# RevisionB.net
KiCad netlist of a schematic drawn in EAGLE
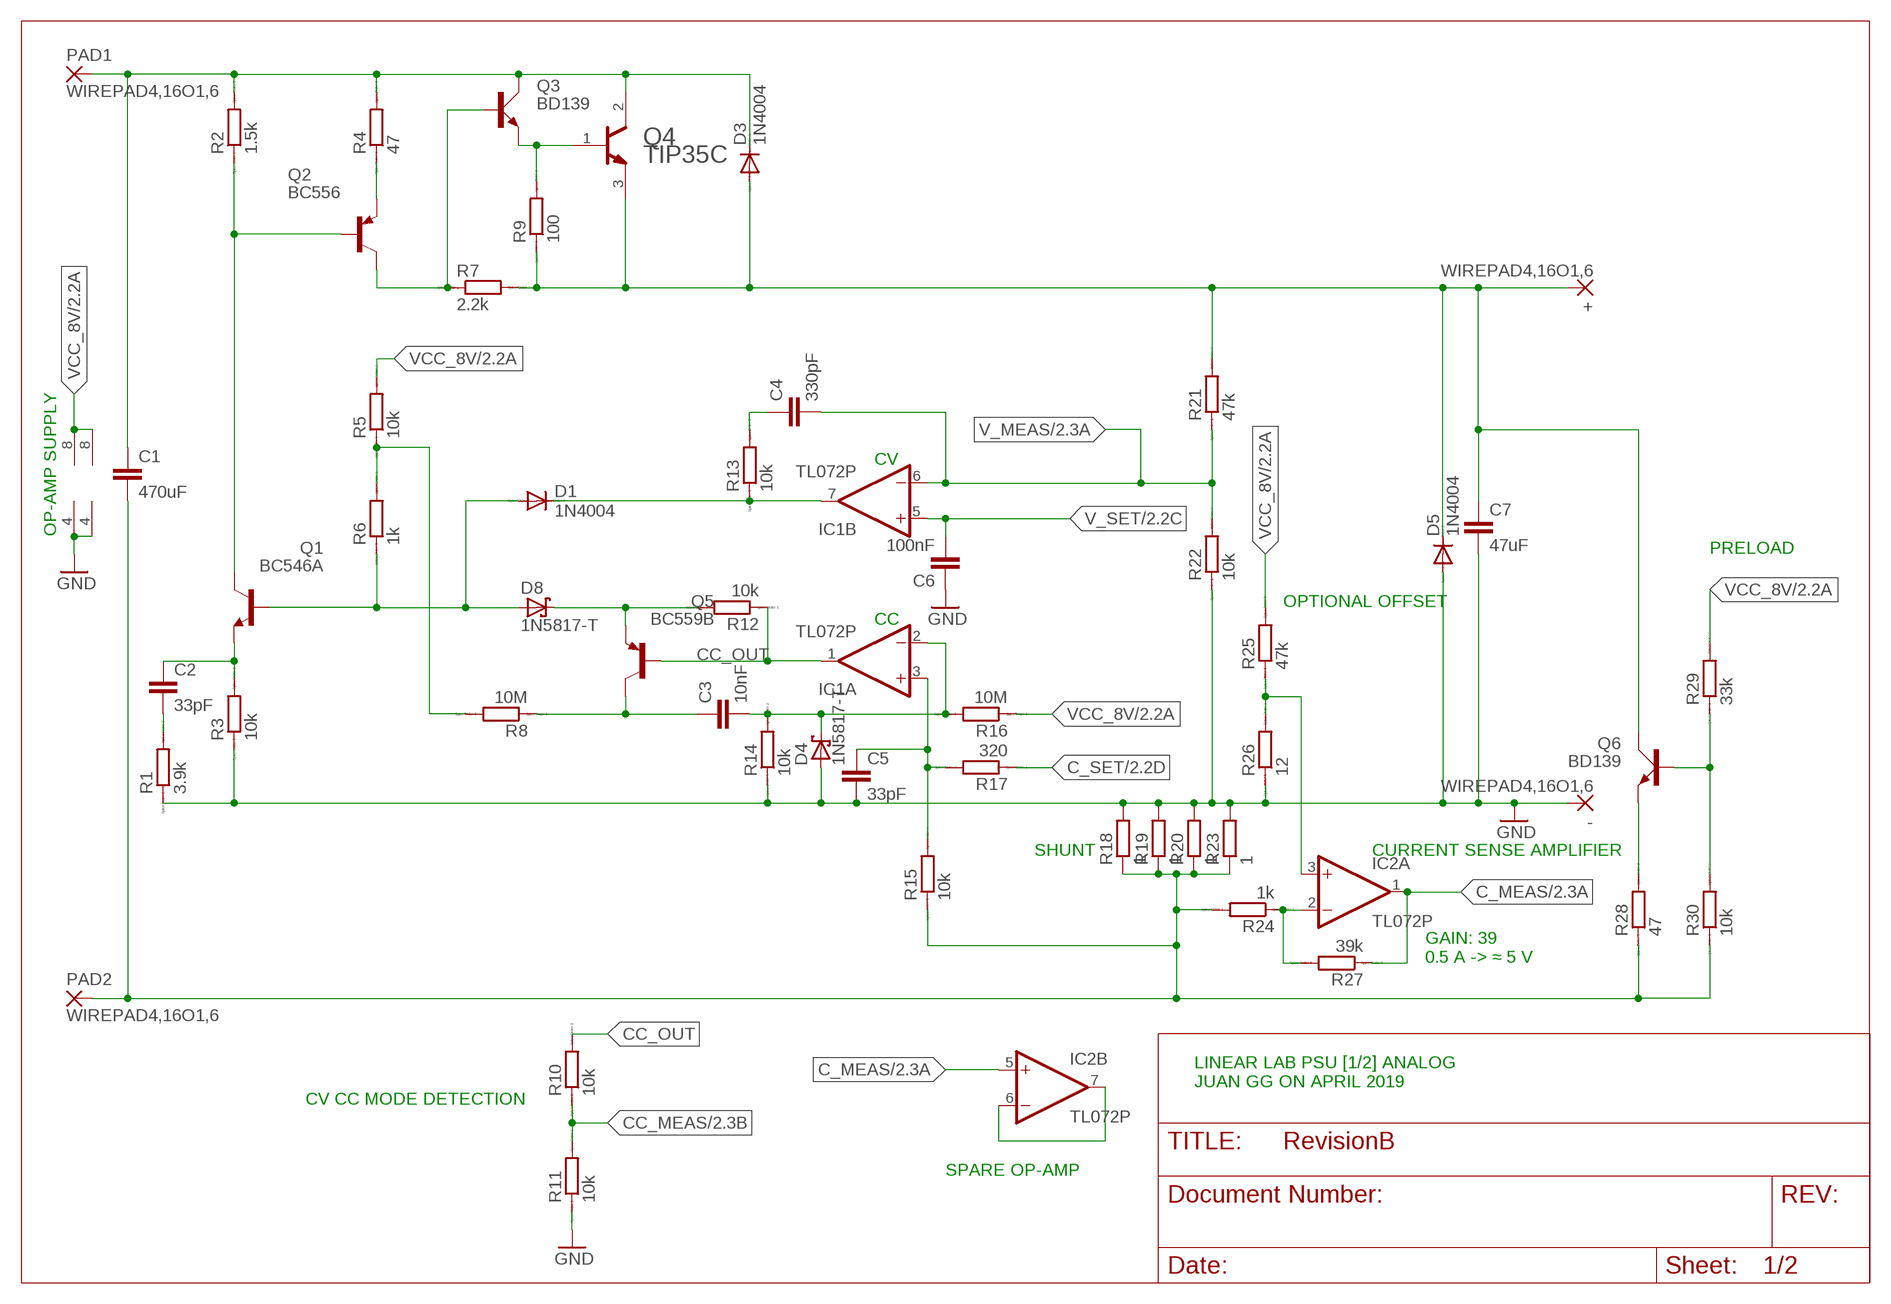
[diagram p0: schematic, sheet 1]
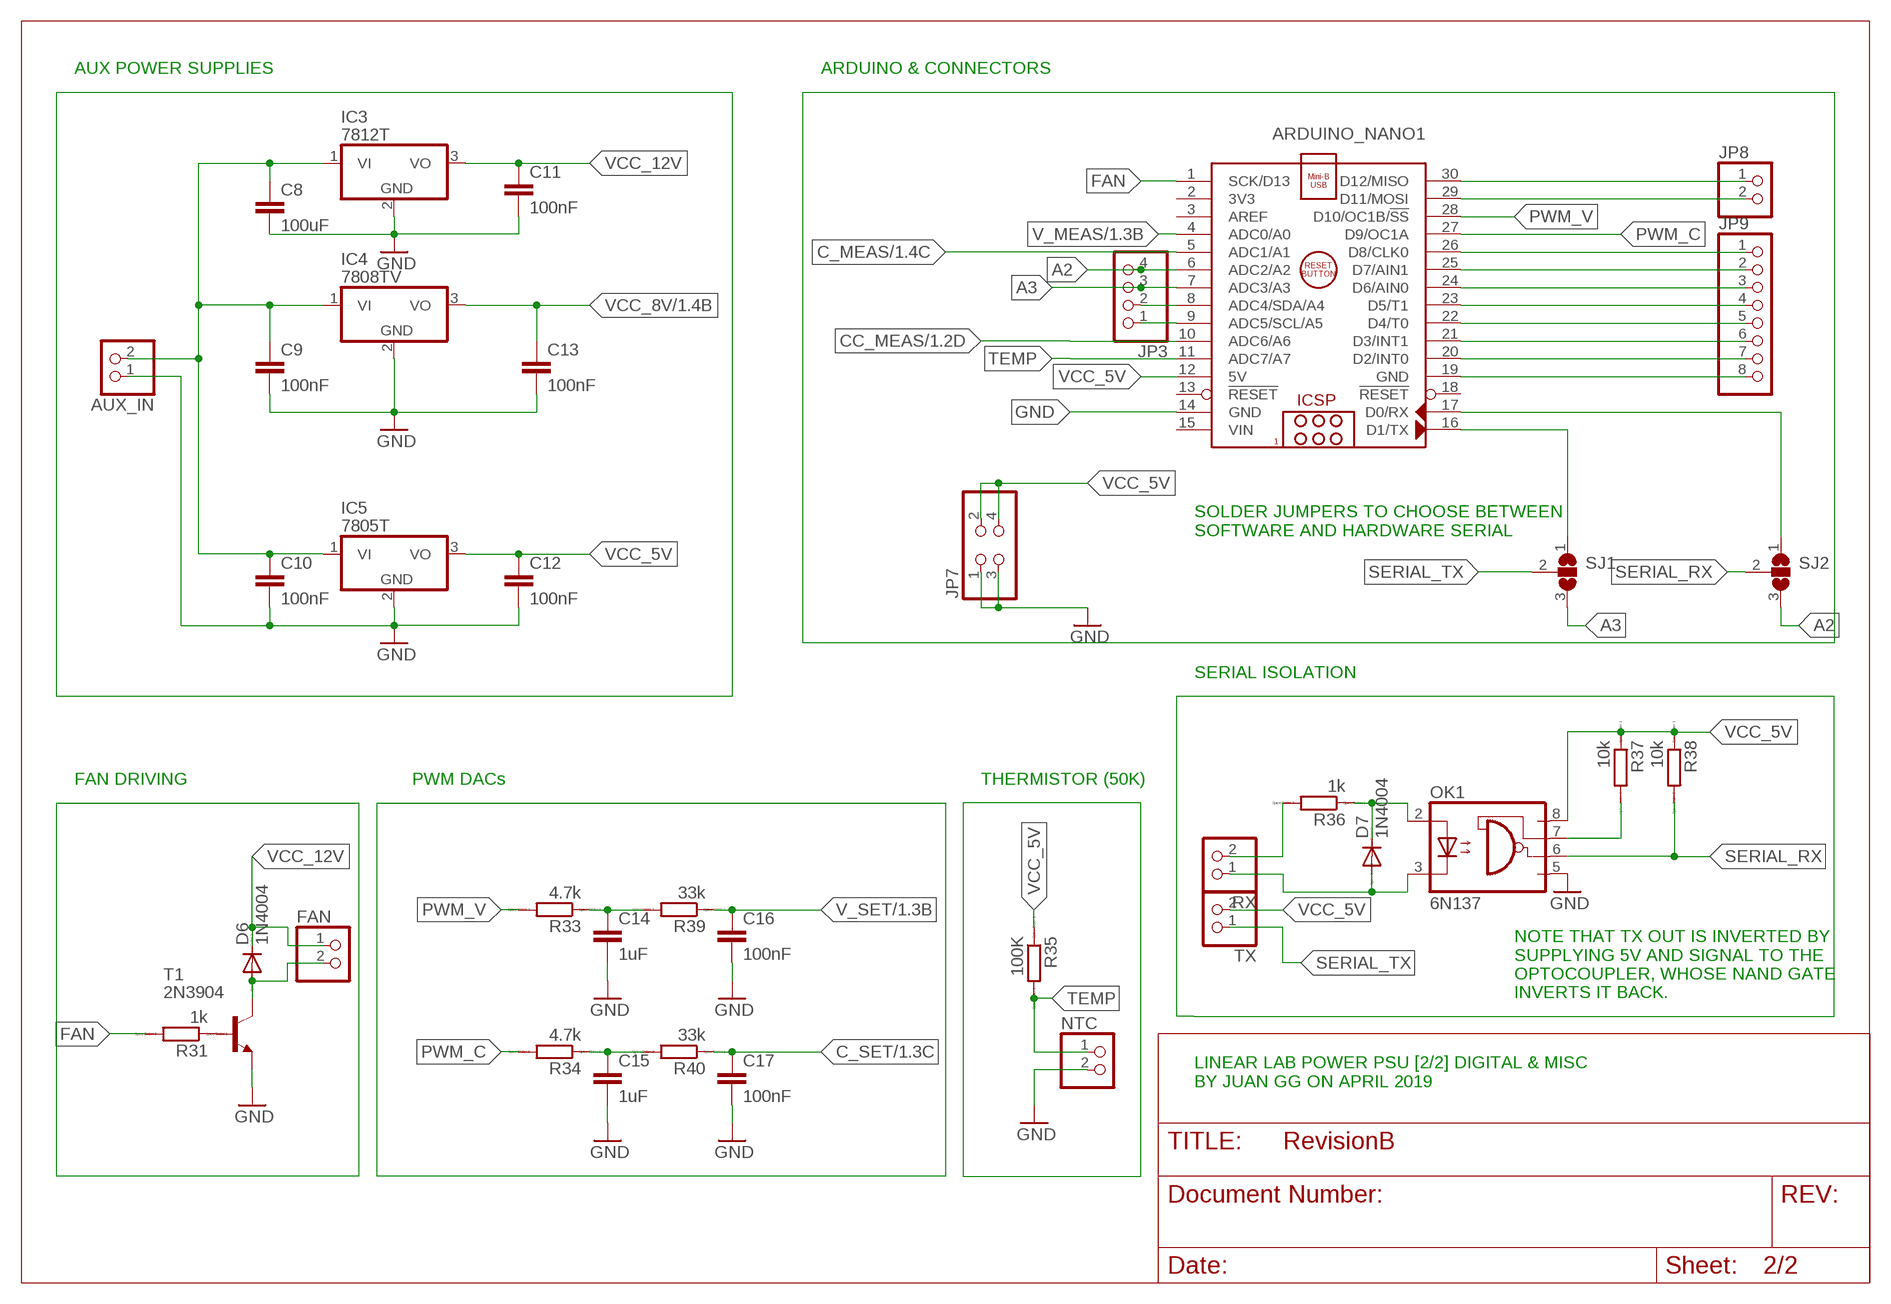
[diagram p1: schematic, sheet 2]

(export (version "E")
  (design (tool "Eeschema 10.0.6"))
  (components
    (comp (ref "+")
      (value "WIREPAD4,16O1,6")
      (footprint "eagle-import:4,16O1,6")
      (libsource (lib "eagle-import") (part "WIREPAD4,16O1,6"))
    )
    (comp (ref "-")
      (value "WIREPAD4,16O1,6")
      (footprint "eagle-import:4,16O1,6")
      (libsource (lib "eagle-import") (part "WIREPAD4,16O1,6"))
    )
    (comp (ref "C1")
      (value "470uF")
      (footprint "eagle-import:C5B7.2")
      (libsource (lib "eagle-import") (part "C5/7.2"))
    )
    (comp (ref "C2")
      (value "33pF")
      (footprint "eagle-import:C2.5-2")
      (libsource (lib "eagle-import") (part "C2.5/2"))
    )
    (comp (ref "C3")
      (value "10nF")
      (footprint "eagle-import:C2.5-2")
      (libsource (lib "eagle-import") (part "C2.5/2"))
    )
    (comp (ref "C4")
      (value "330pF")
      (footprint "eagle-import:C2.5-2")
      (libsource (lib "eagle-import") (part "C2.5/2"))
    )
    (comp (ref "C5")
      (value "33pF")
      (footprint "eagle-import:C2.5-2")
      (libsource (lib "eagle-import") (part "C2.5/2"))
    )
    (comp (ref "C6")
      (value "100nF")
      (footprint "eagle-import:C2.5-2")
      (libsource (lib "eagle-import") (part "C2.5/2"))
    )
    (comp (ref "C7")
      (value "47uF")
      (footprint "eagle-import:C5B7.2")
      (libsource (lib "eagle-import") (part "C5/7.2"))
    )
    (comp (ref "D1")
      (value "1N4004")
      (footprint "eagle-import:DO41-10")
      (libsource (lib "eagle-import") (part "1N4004"))
    )
    (comp (ref "D3")
      (value "1N4004")
      (footprint "eagle-import:DO41-10")
      (libsource (lib "eagle-import") (part "1N4004"))
    )
    (comp (ref "D4")
      (value "1N5817-T")
      (footprint "eagle-import:DO41-7.6")
      (libsource (lib "eagle-import") (part "1N5817-T"))
    )
    (comp (ref "D5")
      (value "1N4004")
      (footprint "eagle-import:DO41-10")
      (libsource (lib "eagle-import") (part "1N4004"))
    )
    (comp (ref "D8")
      (value "1N5817-T")
      (footprint "eagle-import:DO41-7.6")
      (libsource (lib "eagle-import") (part "1N5817-T"))
    )
    (comp (ref "IC1")
      (value "TL072P")
      (footprint "eagle-import:DIL08")
      (libsource (lib "eagle-import") (part "TL072P"))
    )
    (comp (ref "IC2")
      (value "TL072P")
      (footprint "eagle-import:DIL08")
      (libsource (lib "eagle-import") (part "TL072P"))
    )
    (comp (ref "PAD1")
      (value "WIREPAD4,16O1,6")
      (footprint "eagle-import:4,16O1,6")
      (libsource (lib "eagle-import") (part "WIREPAD4,16O1,6"))
    )
    (comp (ref "PAD2")
      (value "WIREPAD4,16O1,6")
      (footprint "eagle-import:4,16O1,6")
      (libsource (lib "eagle-import") (part "WIREPAD4,16O1,6"))
    )
    (comp (ref "Q1")
      (value "BC546A")
      (footprint "eagle-import:TO92-EBC")
      (libsource (lib "eagle-import") (part "BC546A"))
    )
    (comp (ref "Q2")
      (value "BC556")
      (footprint "eagle-import:TO92-EBC")
      (libsource (lib "eagle-import") (part "BC556"))
    )
    (comp (ref "Q3")
      (value "BD139")
      (footprint "eagle-import:TO126AV")
      (libsource (lib "eagle-import") (part "BD139"))
    )
    (comp (ref "Q4")
      (value "STMICROELECTRONICS_TIP35CSTMICROELECTRONICS_TIP35C_0_0")
      (footprint "eagle-import:STMICROELECTRONICS_TIP35C_0")
      (fields
        (field (name "DIGIKEY_PART_NUMBER") "497-2609-5-ND")
        (field (name "MF") "STMicroelectronics")
        (field (name "MOUSER_PART_NUMBER") "511-TIP35C")
      )
      (libsource (lib "eagle-import") (part "STMICROELECTRONICS_TIP35CSTMICROELECTRONICS_TIP35C_0_0"))
    )
    (comp (ref "Q5")
      (value "BC559B")
      (footprint "eagle-import:TO92-EBC")
      (libsource (lib "eagle-import") (part "BC559B"))
    )
    (comp (ref "Q6")
      (value "BD139")
      (footprint "eagle-import:TO126AV")
      (libsource (lib "eagle-import") (part "BD139"))
    )
    (comp (ref "R1")
      (value "3.9k")
      (footprint "eagle-import:0207_10")
      (libsource (lib "eagle-import") (part "R0207/10"))
    )
    (comp (ref "R2")
      (value "1.5k")
      (footprint "eagle-import:0207_10")
      (libsource (lib "eagle-import") (part "R0207/10"))
    )
    (comp (ref "R3")
      (value "10k")
      (footprint "eagle-import:0207_10")
      (libsource (lib "eagle-import") (part "R0207/10"))
    )
    (comp (ref "R4")
      (value "47")
      (footprint "eagle-import:0207_10")
      (libsource (lib "eagle-import") (part "R0207/10"))
    )
    (comp (ref "R5")
      (value "10k")
      (footprint "eagle-import:0207_10")
      (libsource (lib "eagle-import") (part "R0207/10"))
    )
    (comp (ref "R6")
      (value "1k")
      (footprint "eagle-import:0207_10")
      (libsource (lib "eagle-import") (part "R0207/10"))
    )
    (comp (ref "R7")
      (value "2.2k")
      (footprint "eagle-import:0207_10")
      (libsource (lib "eagle-import") (part "R0207/10"))
    )
    (comp (ref "R8")
      (value "10M")
      (footprint "eagle-import:0207_10")
      (libsource (lib "eagle-import") (part "R0207/10"))
    )
    (comp (ref "R9")
      (value "100")
      (footprint "eagle-import:0207_10")
      (libsource (lib "eagle-import") (part "R0207/10"))
    )
    (comp (ref "R10")
      (value "10k")
      (footprint "eagle-import:0207_10")
      (libsource (lib "eagle-import") (part "R0207/10"))
    )
    (comp (ref "R11")
      (value "10k")
      (footprint "eagle-import:0207_10")
      (libsource (lib "eagle-import") (part "R0207/10"))
    )
    (comp (ref "R12")
      (value "10k")
      (footprint "eagle-import:0207_10")
      (libsource (lib "eagle-import") (part "R0207/10"))
    )
    (comp (ref "R13")
      (value "10k")
      (footprint "eagle-import:0207_10")
      (libsource (lib "eagle-import") (part "R0207/10"))
    )
    (comp (ref "R14")
      (value "10k")
      (footprint "eagle-import:0207_10")
      (libsource (lib "eagle-import") (part "R0207/10"))
    )
    (comp (ref "R15")
      (value "10k")
      (footprint "eagle-import:0207_10")
      (libsource (lib "eagle-import") (part "R0207/10"))
    )
    (comp (ref "R16")
      (value "10M")
      (footprint "eagle-import:0207_10")
      (libsource (lib "eagle-import") (part "R0207/10"))
    )
    (comp (ref "R17")
      (value "320")
      (footprint "eagle-import:0207_10")
      (libsource (lib "eagle-import") (part "R0207/10"))
    )
    (comp (ref "R18")
      (value "1")
      (footprint "eagle-import:0617V")
      (libsource (lib "eagle-import") (part "R-EU_0617/5V"))
    )
    (comp (ref "R19")
      (value "1")
      (footprint "eagle-import:0617V")
      (libsource (lib "eagle-import") (part "R-EU_0617/5V"))
    )
    (comp (ref "R20")
      (value "1")
      (footprint "eagle-import:0617V")
      (libsource (lib "eagle-import") (part "R-EU_0617/5V"))
    )
    (comp (ref "R21")
      (value "47k")
      (footprint "eagle-import:0207_10")
      (libsource (lib "eagle-import") (part "R0207/10"))
    )
    (comp (ref "R22")
      (value "10k")
      (footprint "eagle-import:0207_10")
      (libsource (lib "eagle-import") (part "R0207/10"))
    )
    (comp (ref "R23")
      (value "1")
      (footprint "eagle-import:0617V")
      (libsource (lib "eagle-import") (part "R-EU_0617/5V"))
    )
    (comp (ref "R24")
      (value "1k")
      (footprint "eagle-import:0207_10")
      (libsource (lib "eagle-import") (part "R0207/10"))
    )
    (comp (ref "R25")
      (value "47k")
      (footprint "eagle-import:0207_10")
      (libsource (lib "eagle-import") (part "R0207/10"))
    )
    (comp (ref "R26")
      (value "12")
      (footprint "eagle-import:0207_10")
      (libsource (lib "eagle-import") (part "R0207/10"))
    )
    (comp (ref "R27")
      (value "39k")
      (footprint "eagle-import:0207_10")
      (libsource (lib "eagle-import") (part "R0207/10"))
    )
    (comp (ref "R28")
      (value "47")
      (footprint "eagle-import:0207_10")
      (libsource (lib "eagle-import") (part "R0207/10"))
    )
    (comp (ref "R29")
      (value "33k")
      (footprint "eagle-import:0207_10")
      (libsource (lib "eagle-import") (part "R0207/10"))
    )
    (comp (ref "R30")
      (value "10k")
      (footprint "eagle-import:0207_10")
      (libsource (lib "eagle-import") (part "R0207/10"))
    )
    (comp (ref "ARDUINO_NANO1")
      (value "ARDUINO_NANO")
      (footprint "eagle-import:ARDUINO_NANO")
      (libsource (lib "eagle-import") (part "ARDUINO_NANO"))
    )
    (comp (ref "AUX_IN")
      (value "PINHD-1X2")
      (footprint "eagle-import:1X02")
      (libsource (lib "eagle-import") (part "PINHD-1X2"))
    )
    (comp (ref "C8")
      (value "100uF")
      (footprint "eagle-import:C2.5-4")
      (libsource (lib "eagle-import") (part "C2.5/4"))
    )
    (comp (ref "C9")
      (value "100nF")
      (footprint "eagle-import:C2.5-2")
      (libsource (lib "eagle-import") (part "C2.5/2"))
    )
    (comp (ref "C10")
      (value "100nF")
      (footprint "eagle-import:C2.5-2")
      (libsource (lib "eagle-import") (part "C2.5/2"))
    )
    (comp (ref "C11")
      (value "100nF")
      (footprint "eagle-import:C2.5-2")
      (libsource (lib "eagle-import") (part "C2.5/2"))
    )
    (comp (ref "C12")
      (value "100nF")
      (footprint "eagle-import:C2.5-2")
      (libsource (lib "eagle-import") (part "C2.5/2"))
    )
    (comp (ref "C13")
      (value "100nF")
      (footprint "eagle-import:C2.5-2")
      (libsource (lib "eagle-import") (part "C2.5/2"))
    )
    (comp (ref "C14")
      (value "1uF")
      (footprint "eagle-import:C2.5-4")
      (libsource (lib "eagle-import") (part "C2.5/4"))
    )
    (comp (ref "C15")
      (value "1uF")
      (footprint "eagle-import:C2.5-4")
      (libsource (lib "eagle-import") (part "C2.5/4"))
    )
    (comp (ref "C16")
      (value "100nF")
      (footprint "eagle-import:C2.5-4")
      (libsource (lib "eagle-import") (part "C2.5/4"))
    )
    (comp (ref "C17")
      (value "100nF")
      (footprint "eagle-import:C2.5-4")
      (libsource (lib "eagle-import") (part "C2.5/4"))
    )
    (comp (ref "D6")
      (value "1N4004")
      (footprint "eagle-import:DO41-10")
      (libsource (lib "eagle-import") (part "1N4004"))
    )
    (comp (ref "D7")
      (value "1N4004")
      (footprint "eagle-import:DO41-10")
      (libsource (lib "eagle-import") (part "1N4004"))
    )
    (comp (ref "FAN")
      (value "PINHD-1X2")
      (footprint "eagle-import:1X02")
      (libsource (lib "eagle-import") (part "PINHD-1X2"))
    )
    (comp (ref "IC3")
      (value "7812T")
      (footprint "eagle-import:TO220H")
      (libsource (lib "eagle-import") (part "78T12"))
    )
    (comp (ref "IC4")
      (value "7808TV")
      (footprint "eagle-import:TO220H")
      (libsource (lib "eagle-import") (part "78T12"))
    )
    (comp (ref "IC5")
      (value "7805T")
      (footprint "eagle-import:TO220H")
      (libsource (lib "eagle-import") (part "78T05"))
    )
    (comp (ref "JP3")
      (value "PINHD-1X4")
      (footprint "eagle-import:1X04")
      (libsource (lib "eagle-import") (part "PINHD-1X4"))
    )
    (comp (ref "JP7")
      (value "PINHD-2X2")
      (footprint "eagle-import:2X02")
      (libsource (lib "eagle-import") (part "PINHD-2X2"))
    )
    (comp (ref "JP8")
      (value "PINHD-1X2")
      (footprint "eagle-import:1X02")
      (libsource (lib "eagle-import") (part "PINHD-1X2"))
    )
    (comp (ref "JP9")
      (value "PINHD-1X8")
      (footprint "eagle-import:1X08")
      (libsource (lib "eagle-import") (part "PINHD-1X8"))
    )
    (comp (ref "NTC")
      (value "PINHD-1X2")
      (footprint "eagle-import:1X02")
      (libsource (lib "eagle-import") (part "PINHD-1X2"))
    )
    (comp (ref "OK1")
      (value "6N137")
      (footprint "eagle-import:DIL08")
      (libsource (lib "eagle-import") (part "6N137"))
    )
    (comp (ref "R31")
      (value "1k")
      (footprint "eagle-import:0207_10")
      (libsource (lib "eagle-import") (part "R0207/10"))
    )
    (comp (ref "R33")
      (value "4.7k")
      (footprint "eagle-import:0207_10")
      (libsource (lib "eagle-import") (part "R0207/10"))
    )
    (comp (ref "R34")
      (value "4.7k")
      (footprint "eagle-import:0207_10")
      (libsource (lib "eagle-import") (part "R0207/10"))
    )
    (comp (ref "R35")
      (value "100K")
      (footprint "eagle-import:0207_10")
      (libsource (lib "eagle-import") (part "R0207/10"))
    )
    (comp (ref "R36")
      (value "1k")
      (footprint "eagle-import:0207_10")
      (libsource (lib "eagle-import") (part "R0207/10"))
    )
    (comp (ref "R37")
      (value "10k")
      (footprint "eagle-import:0207_10")
      (libsource (lib "eagle-import") (part "R0207/10"))
    )
    (comp (ref "R38")
      (value "10k")
      (footprint "eagle-import:0207_10")
      (libsource (lib "eagle-import") (part "R0207/10"))
    )
    (comp (ref "R39")
      (value "33k")
      (footprint "eagle-import:0207_10")
      (libsource (lib "eagle-import") (part "R0207/10"))
    )
    (comp (ref "R40")
      (value "33k")
      (footprint "eagle-import:0207_10")
      (libsource (lib "eagle-import") (part "R0207/10"))
    )
    (comp (ref "RX")
      (value "PINHD-1X2")
      (footprint "eagle-import:1X02")
      (libsource (lib "eagle-import") (part "PINHD-1X2"))
    )
    (comp (ref "SJ1")
      (value "SJ2W")
      (footprint "eagle-import:SJ_2")
      (libsource (lib "eagle-import") (part "SJ2W"))
    )
    (comp (ref "SJ2")
      (value "SJ2W")
      (footprint "eagle-import:SJ_2")
      (libsource (lib "eagle-import") (part "SJ2W"))
    )
    (comp (ref "T1")
      (value "2N3904")
      (footprint "eagle-import:TO92")
      (libsource (lib "eagle-import") (part "2N3904"))
    )
    (comp (ref "TX")
      (value "PINHD-1X2")
      (footprint "eagle-import:1X02")
      (libsource (lib "eagle-import") (part "PINHD-1X2"))
    )
  )
  (nets
    (net (code "1") (name "A2") (class "Default")
      (node (ref "ARDUINO_NANO1") (pin "6") (pinfunction "ADC2/A2_6") (pintype "bidirectional"))
      (node (ref "JP3") (pin "4") (pinfunction "4_4") (pintype "passive"))
      (node (ref "SJ2") (pin "3") (pinfunction "3_3") (pintype "passive"))
    )
    (net (code "2") (name "A3") (class "Default")
      (node (ref "ARDUINO_NANO1") (pin "7") (pinfunction "ADC3/A3_7") (pintype "bidirectional"))
      (node (ref "JP3") (pin "3") (pinfunction "3_3") (pintype "passive"))
      (node (ref "SJ1") (pin "3") (pinfunction "3_3") (pintype "passive"))
    )
    (net (code "3") (name "CC_MEAS") (class "Default")
      (node (ref "ARDUINO_NANO1") (pin "10") (pinfunction "ADC6/A6_10") (pintype "bidirectional"))
      (node (ref "R10") (pin "1") (pinfunction "1_1") (pintype "passive"))
      (node (ref "R11") (pin "2") (pinfunction "2_2") (pintype "passive"))
    )
    (net (code "4") (name "CC_OUT") (class "Default")
      (node (ref "IC1") (pin "1") (pinfunction "OUT_1") (pintype "output"))
      (node (ref "Q5") (pin "B") (pinfunction "B_B") (pintype "passive"))
      (node (ref "R10") (pin "2") (pinfunction "2_2") (pintype "passive"))
      (node (ref "R12") (pin "1") (pinfunction "1_1") (pintype "passive"))
    )
    (net (code "5") (name "C_MEAS") (class "Default")
      (node (ref "ARDUINO_NANO1") (pin "5") (pinfunction "ADC1/A1_5") (pintype "bidirectional"))
      (node (ref "IC2") (pin "1") (pinfunction "OUT_1") (pintype "output"))
      (node (ref "IC2") (pin "5") (pinfunction "+IN_5") (pintype "input"))
      (node (ref "R27") (pin "1") (pinfunction "1_1") (pintype "passive"))
    )
    (net (code "6") (name "C_SET") (class "Default")
      (node (ref "C17") (pin "1") (pinfunction "1_1") (pintype "passive"))
      (node (ref "R17") (pin "1") (pinfunction "1_1") (pintype "passive"))
      (node (ref "R40") (pin "1") (pinfunction "1_1") (pintype "passive"))
    )
    (net (code "7") (name "FAN") (class "Default")
      (node (ref "ARDUINO_NANO1") (pin "1") (pinfunction "SCK/D13_1") (pintype "bidirectional"))
      (node (ref "R31") (pin "2") (pinfunction "2_2") (pintype "passive"))
    )
    (net (code "8") (name "GND") (class "Default")
      (node (ref "-") (pin "1") (pinfunction "P_1") (pintype "passive"))
      (node (ref "ARDUINO_NANO1") (pin "14") (pinfunction "GND_14") (pintype "power_in"))
      (node (ref "ARDUINO_NANO1") (pin "19") (pinfunction "GND_19") (pintype "power_in"))
      (node (ref "AUX_IN") (pin "1") (pinfunction "1_1") (pintype "passive"))
      (node (ref "C10") (pin "2") (pinfunction "2_2") (pintype "passive"))
      (node (ref "C11") (pin "2") (pinfunction "2_2") (pintype "passive"))
      (node (ref "C12") (pin "2") (pinfunction "2_2") (pintype "passive"))
      (node (ref "C13") (pin "2") (pinfunction "2_2") (pintype "passive"))
      (node (ref "C14") (pin "2") (pinfunction "2_2") (pintype "passive"))
      (node (ref "C15") (pin "2") (pinfunction "2_2") (pintype "passive"))
      (node (ref "C16") (pin "2") (pinfunction "2_2") (pintype "passive"))
      (node (ref "C17") (pin "2") (pinfunction "2_2") (pintype "passive"))
      (node (ref "C5") (pin "2") (pinfunction "2_2") (pintype "passive"))
      (node (ref "C6") (pin "1") (pinfunction "1_1") (pintype "passive"))
      (node (ref "C7") (pin "2") (pinfunction "2_2") (pintype "passive"))
      (node (ref "C8") (pin "2") (pinfunction "2_2") (pintype "passive"))
      (node (ref "C9") (pin "2") (pinfunction "2_2") (pintype "passive"))
      (node (ref "D4") (pin "A") (pinfunction "A_A") (pintype "passive"))
      (node (ref "D5") (pin "A") (pinfunction "A_A") (pintype "passive"))
      (node (ref "IC1") (pin "4") (pinfunction "V-_4") (pintype "power_in"))
      (node (ref "IC2") (pin "4") (pinfunction "V-_4") (pintype "power_in"))
      (node (ref "IC3") (pin "2") (pinfunction "GND_2") (pintype "passive"))
      (node (ref "IC4") (pin "2") (pinfunction "GND_2") (pintype "passive"))
      (node (ref "IC5") (pin "2") (pinfunction "GND_2") (pintype "passive"))
      (node (ref "JP7") (pin "1") (pinfunction "1_1") (pintype "passive"))
      (node (ref "JP7") (pin "3") (pinfunction "3_3") (pintype "passive"))
      (node (ref "JP9") (pin "8") (pinfunction "8_8") (pintype "passive"))
      (node (ref "NTC") (pin "2") (pinfunction "2_2") (pintype "passive"))
      (node (ref "OK1") (pin "5") (pinfunction "GND_5") (pintype "passive"))
      (node (ref "R1") (pin "1") (pinfunction "1_1") (pintype "passive"))
      (node (ref "R11") (pin "1") (pinfunction "1_1") (pintype "passive"))
      (node (ref "R14") (pin "1") (pinfunction "1_1") (pintype "passive"))
      (node (ref "R18") (pin "2") (pinfunction "2_2") (pintype "passive"))
      (node (ref "R19") (pin "2") (pinfunction "2_2") (pintype "passive"))
      (node (ref "R20") (pin "2") (pinfunction "2_2") (pintype "passive"))
      (node (ref "R22") (pin "1") (pinfunction "1_1") (pintype "passive"))
      (node (ref "R23") (pin "2") (pinfunction "2_2") (pintype "passive"))
      (node (ref "R26") (pin "1") (pinfunction "1_1") (pintype "passive"))
      (node (ref "R3") (pin "1") (pinfunction "1_1") (pintype "passive"))
      (node (ref "T1") (pin "3") (pinfunction "E_3") (pintype "passive"))
    )
    (net (code "9") (name "Net-(+-P)") (class "Default")
      (node (ref "+") (pin "1") (pinfunction "P_1") (pintype "passive"))
      (node (ref "C7") (pin "1") (pinfunction "1_1") (pintype "passive"))
      (node (ref "D3") (pin "A") (pinfunction "A_A") (pintype "passive"))
      (node (ref "D5") (pin "C") (pinfunction "C_C") (pintype "passive"))
      (node (ref "Q4") (pin "3") (pinfunction "EMITTER_3") (pintype "bidirectional"))
      (node (ref "Q6") (pin "C") (pinfunction "C_C") (pintype "passive"))
      (node (ref "R21") (pin "2") (pinfunction "2_2") (pintype "passive"))
      (node (ref "R7") (pin "2") (pinfunction "2_2") (pintype "passive"))
      (node (ref "R9") (pin "1") (pinfunction "1_1") (pintype "passive"))
    )
    (net (code "10") (name "Net-(ARDUINO_NANO1-ADC4{slash}SDA{slash}A4)") (class "Default")
      (node (ref "ARDUINO_NANO1") (pin "8") (pinfunction "ADC4/SDA/A4_8") (pintype "bidirectional"))
      (node (ref "JP3") (pin "2") (pinfunction "2_2") (pintype "passive"))
    )
    (net (code "11") (name "Net-(ARDUINO_NANO1-ADC5{slash}SCL{slash}A5)") (class "Default")
      (node (ref "ARDUINO_NANO1") (pin "9") (pinfunction "ADC5/SCL/A5_9") (pintype "bidirectional"))
      (node (ref "JP3") (pin "1") (pinfunction "1_1") (pintype "passive"))
    )
    (net (code "12") (name "Net-(ARDUINO_NANO1-D0{slash}RX)") (class "Default")
      (node (ref "ARDUINO_NANO1") (pin "17") (pinfunction "D0/RX_17") (pintype "bidirectional"))
      (node (ref "SJ2") (pin "1") (pinfunction "1_1") (pintype "passive"))
    )
    (net (code "13") (name "Net-(ARDUINO_NANO1-D1{slash}TX)") (class "Default")
      (node (ref "ARDUINO_NANO1") (pin "16") (pinfunction "D1/TX_16") (pintype "bidirectional"))
      (node (ref "SJ1") (pin "1") (pinfunction "1_1") (pintype "passive"))
    )
    (net (code "14") (name "Net-(ARDUINO_NANO1-D2{slash}INT0)") (class "Default")
      (node (ref "ARDUINO_NANO1") (pin "20") (pinfunction "D2/INT0_20") (pintype "bidirectional"))
      (node (ref "JP9") (pin "7") (pinfunction "7_7") (pintype "passive"))
    )
    (net (code "15") (name "Net-(ARDUINO_NANO1-D3{slash}INT1)") (class "Default")
      (node (ref "ARDUINO_NANO1") (pin "21") (pinfunction "D3/INT1_21") (pintype "bidirectional"))
      (node (ref "JP9") (pin "6") (pinfunction "6_6") (pintype "passive"))
    )
    (net (code "16") (name "Net-(ARDUINO_NANO1-D4{slash}T0)") (class "Default")
      (node (ref "ARDUINO_NANO1") (pin "22") (pinfunction "D4/T0_22") (pintype "bidirectional"))
      (node (ref "JP9") (pin "5") (pinfunction "5_5") (pintype "passive"))
    )
    (net (code "17") (name "Net-(ARDUINO_NANO1-D5{slash}T1)") (class "Default")
      (node (ref "ARDUINO_NANO1") (pin "23") (pinfunction "D5/T1_23") (pintype "bidirectional"))
      (node (ref "JP9") (pin "4") (pinfunction "4_4") (pintype "passive"))
    )
    (net (code "18") (name "Net-(ARDUINO_NANO1-D6{slash}AIN0)") (class "Default")
      (node (ref "ARDUINO_NANO1") (pin "24") (pinfunction "D6/AIN0_24") (pintype "bidirectional"))
      (node (ref "JP9") (pin "3") (pinfunction "3_3") (pintype "passive"))
    )
    (net (code "19") (name "Net-(ARDUINO_NANO1-D7{slash}AIN1)") (class "Default")
      (node (ref "ARDUINO_NANO1") (pin "25") (pinfunction "D7/AIN1_25") (pintype "bidirectional"))
      (node (ref "JP9") (pin "2") (pinfunction "2_2") (pintype "passive"))
    )
    (net (code "20") (name "Net-(ARDUINO_NANO1-D8{slash}CLK0)") (class "Default")
      (node (ref "ARDUINO_NANO1") (pin "26") (pinfunction "D8/CLK0_26") (pintype "bidirectional"))
      (node (ref "JP9") (pin "1") (pinfunction "1_1") (pintype "passive"))
    )
    (net (code "21") (name "Net-(ARDUINO_NANO1-D11{slash}MOSI)") (class "Default")
      (node (ref "ARDUINO_NANO1") (pin "29") (pinfunction "D11/MOSI_29") (pintype "bidirectional"))
      (node (ref "JP8") (pin "2") (pinfunction "2_2") (pintype "passive"))
    )
    (net (code "22") (name "Net-(ARDUINO_NANO1-D12{slash}MISO)") (class "Default")
      (node (ref "ARDUINO_NANO1") (pin "30") (pinfunction "D12/MISO_30") (pintype "bidirectional"))
      (node (ref "JP8") (pin "1") (pinfunction "1_1") (pintype "passive"))
    )
    (net (code "23") (name "Net-(C2-Pad1)") (class "Default")
      (node (ref "C2") (pin "1") (pinfunction "1_1") (pintype "passive"))
      (node (ref "Q1") (pin "E") (pinfunction "E_E") (pintype "passive"))
      (node (ref "R3") (pin "2") (pinfunction "2_2") (pintype "passive"))
    )
    (net (code "24") (name "Net-(C2-Pad2)") (class "Default")
      (node (ref "C2") (pin "2") (pinfunction "2_2") (pintype "passive"))
      (node (ref "R1") (pin "2") (pinfunction "2_2") (pintype "passive"))
    )
    (net (code "25") (name "Net-(C3-Pad1)") (class "Default")
      (node (ref "C3") (pin "1") (pinfunction "1_1") (pintype "passive"))
      (node (ref "Q5") (pin "C") (pinfunction "C_C") (pintype "passive"))
      (node (ref "R8") (pin "1") (pinfunction "1_1") (pintype "passive"))
    )
    (net (code "26") (name "Net-(C4-Pad1)") (class "Default")
      (node (ref "C4") (pin "1") (pinfunction "1_1") (pintype "passive"))
      (node (ref "R13") (pin "2") (pinfunction "2_2") (pintype "passive"))
    )
    (net (code "27") (name "Net-(C14-Pad1)") (class "Default")
      (node (ref "C14") (pin "1") (pinfunction "1_1") (pintype "passive"))
      (node (ref "R33") (pin "1") (pinfunction "1_1") (pintype "passive"))
      (node (ref "R39") (pin "2") (pinfunction "2_2") (pintype "passive"))
    )
    (net (code "28") (name "Net-(C15-Pad1)") (class "Default")
      (node (ref "C15") (pin "1") (pinfunction "1_1") (pintype "passive"))
      (node (ref "R34") (pin "1") (pinfunction "1_1") (pintype "passive"))
      (node (ref "R40") (pin "2") (pinfunction "2_2") (pintype "passive"))
    )
    (net (code "29") (name "Net-(D1-PadA)") (class "Default")
      (node (ref "D1") (pin "A") (pinfunction "A_A") (pintype "passive"))
      (node (ref "D8") (pin "A") (pinfunction "A_A") (pintype "passive"))
      (node (ref "Q1") (pin "B") (pinfunction "B_B") (pintype "passive"))
      (node (ref "R6") (pin "1") (pinfunction "1_1") (pintype "passive"))
    )
    (net (code "30") (name "Net-(D8-PadC)") (class "Default")
      (node (ref "D8") (pin "C") (pinfunction "C_C") (pintype "passive"))
      (node (ref "Q5") (pin "E") (pinfunction "E_E") (pintype "passive"))
      (node (ref "R12") (pin "2") (pinfunction "2_2") (pintype "passive"))
    )
    (net (code "31") (name "Net-(IC1A-+IN)") (class "Default")
      (node (ref "C5") (pin "1") (pinfunction "1_1") (pintype "passive"))
      (node (ref "IC1") (pin "3") (pinfunction "+IN_3") (pintype "input"))
      (node (ref "R15") (pin "2") (pinfunction "2_2") (pintype "passive"))
      (node (ref "R17") (pin "2") (pinfunction "2_2") (pintype "passive"))
    )
    (net (code "32") (name "Net-(IC1A--IN)") (class "Default")
      (node (ref "C3") (pin "2") (pinfunction "2_2") (pintype "passive"))
      (node (ref "D4") (pin "C") (pinfunction "C_C") (pintype "passive"))
      (node (ref "IC1") (pin "2") (pinfunction "-IN_2") (pintype "input"))
      (node (ref "R14") (pin "2") (pinfunction "2_2") (pintype "passive"))
      (node (ref "R16") (pin "2") (pinfunction "2_2") (pintype "passive"))
    )
    (net (code "33") (name "Net-(IC1B-OUT)") (class "Default")
      (node (ref "D1") (pin "C") (pinfunction "C_C") (pintype "passive"))
      (node (ref "IC1") (pin "7") (pinfunction "OUT_7") (pintype "output"))
      (node (ref "R13") (pin "1") (pinfunction "1_1") (pintype "passive"))
    )
    (net (code "34") (name "Net-(IC2A-+IN)") (class "Default")
      (node (ref "IC2") (pin "3") (pinfunction "+IN_3") (pintype "input"))
      (node (ref "R25") (pin "1") (pinfunction "1_1") (pintype "passive"))
      (node (ref "R26") (pin "2") (pinfunction "2_2") (pintype "passive"))
    )
    (net (code "35") (name "Net-(IC2A--IN)") (class "Default")
      (node (ref "IC2") (pin "2") (pinfunction "-IN_2") (pintype "input"))
      (node (ref "R24") (pin "1") (pinfunction "1_1") (pintype "passive"))
      (node (ref "R27") (pin "2") (pinfunction "2_2") (pintype "passive"))
    )
    (net (code "36") (name "Net-(IC2B--IN)") (class "Default")
      (node (ref "IC2") (pin "6") (pinfunction "-IN_6") (pintype "input"))
      (node (ref "IC2") (pin "7") (pinfunction "OUT_7") (pintype "output"))
    )
    (net (code "37") (name "Net-(IC3-VI)") (class "Default")
      (node (ref "AUX_IN") (pin "2") (pinfunction "2_2") (pintype "passive"))
      (node (ref "C10") (pin "1") (pinfunction "1_1") (pintype "passive"))
      (node (ref "C8") (pin "1") (pinfunction "1_1") (pintype "passive"))
      (node (ref "C9") (pin "1") (pinfunction "1_1") (pintype "passive"))
      (node (ref "IC3") (pin "1") (pinfunction "VI_1") (pintype "input"))
      (node (ref "IC4") (pin "1") (pinfunction "VI_1") (pintype "input"))
      (node (ref "IC5") (pin "1") (pinfunction "VI_1") (pintype "input"))
    )
    (net (code "38") (name "Net-(OK1-A)") (class "Default")
      (node (ref "D7") (pin "C") (pinfunction "C_C") (pintype "passive"))
      (node (ref "OK1") (pin "2") (pinfunction "A_2") (pintype "passive"))
      (node (ref "R36") (pin "1") (pinfunction "1_1") (pintype "passive"))
    )
    (net (code "39") (name "Net-(OK1-C)") (class "Default")
      (node (ref "D7") (pin "A") (pinfunction "A_A") (pintype "passive"))
      (node (ref "OK1") (pin "3") (pinfunction "C_3") (pintype "passive"))
      (node (ref "RX") (pin "1") (pinfunction "1_1") (pintype "passive"))
    )
    (net (code "40") (name "Net-(OK1-VE)") (class "Default")
      (node (ref "OK1") (pin "7") (pinfunction "VE_7") (pintype "passive"))
      (node (ref "R37") (pin "2") (pinfunction "2_2") (pintype "passive"))
    )
    (net (code "41") (name "Net-(PAD1-P)") (class "Default")
      (node (ref "C1") (pin "1") (pinfunction "1_1") (pintype "passive"))
      (node (ref "D3") (pin "C") (pinfunction "C_C") (pintype "passive"))
      (node (ref "PAD1") (pin "1") (pinfunction "P_1") (pintype "passive"))
      (node (ref "Q3") (pin "C") (pinfunction "C_C") (pintype "passive"))
      (node (ref "Q4") (pin "2") (pinfunction "COLLECTOR_2") (pintype "bidirectional"))
      (node (ref "R2") (pin "2") (pinfunction "2_2") (pintype "passive"))
      (node (ref "R4") (pin "2") (pinfunction "2_2") (pintype "passive"))
    )
    (net (code "42") (name "Net-(PAD2-P)") (class "Default")
      (node (ref "C1") (pin "2") (pinfunction "2_2") (pintype "passive"))
      (node (ref "PAD2") (pin "1") (pinfunction "P_1") (pintype "passive"))
      (node (ref "R15") (pin "1") (pinfunction "1_1") (pintype "passive"))
      (node (ref "R18") (pin "1") (pinfunction "1_1") (pintype "passive"))
      (node (ref "R19") (pin "1") (pinfunction "1_1") (pintype "passive"))
      (node (ref "R20") (pin "1") (pinfunction "1_1") (pintype "passive"))
      (node (ref "R23") (pin "1") (pinfunction "1_1") (pintype "passive"))
      (node (ref "R24") (pin "2") (pinfunction "2_2") (pintype "passive"))
      (node (ref "R28") (pin "1") (pinfunction "1_1") (pintype "passive"))
      (node (ref "R30") (pin "1") (pinfunction "1_1") (pintype "passive"))
    )
    (net (code "43") (name "Net-(Q1-PadC)") (class "Default")
      (node (ref "Q1") (pin "C") (pinfunction "C_C") (pintype "passive"))
      (node (ref "Q2") (pin "B") (pinfunction "B_B") (pintype "passive"))
      (node (ref "R2") (pin "1") (pinfunction "1_1") (pintype "passive"))
    )
    (net (code "44") (name "Net-(Q2-PadC)") (class "Default")
      (node (ref "Q2") (pin "C") (pinfunction "C_C") (pintype "passive"))
      (node (ref "Q3") (pin "B") (pinfunction "B_B") (pintype "passive"))
      (node (ref "R7") (pin "1") (pinfunction "1_1") (pintype "passive"))
    )
    (net (code "45") (name "Net-(Q2-PadE)") (class "Default")
      (node (ref "Q2") (pin "E") (pinfunction "E_E") (pintype "passive"))
      (node (ref "R4") (pin "1") (pinfunction "1_1") (pintype "passive"))
    )
    (net (code "46") (name "Net-(Q4-BASE)") (class "Default")
      (node (ref "Q3") (pin "E") (pinfunction "E_E") (pintype "passive"))
      (node (ref "Q4") (pin "1") (pinfunction "BASE_1") (pintype "bidirectional"))
      (node (ref "R9") (pin "2") (pinfunction "2_2") (pintype "passive"))
    )
    (net (code "47") (name "Net-(Q6-PadB)") (class "Default")
      (node (ref "Q6") (pin "B") (pinfunction "B_B") (pintype "passive"))
      (node (ref "R29") (pin "1") (pinfunction "1_1") (pintype "passive"))
      (node (ref "R30") (pin "2") (pinfunction "2_2") (pintype "passive"))
    )
    (net (code "48") (name "Net-(Q6-PadE)") (class "Default")
      (node (ref "Q6") (pin "E") (pinfunction "E_E") (pintype "passive"))
      (node (ref "R28") (pin "2") (pinfunction "2_2") (pintype "passive"))
    )
    (net (code "49") (name "Net-(R5-Pad1)") (class "Default")
      (node (ref "R5") (pin "1") (pinfunction "1_1") (pintype "passive"))
      (node (ref "R6") (pin "2") (pinfunction "2_2") (pintype "passive"))
      (node (ref "R8") (pin "2") (pinfunction "2_2") (pintype "passive"))
    )
    (net (code "50") (name "Net-(R36-Pad2)") (class "Default")
      (node (ref "R36") (pin "2") (pinfunction "2_2") (pintype "passive"))
      (node (ref "RX") (pin "2") (pinfunction "2_2") (pintype "passive"))
    )
    (net (code "51") (name "Net-(T1-B)") (class "Default")
      (node (ref "R31") (pin "1") (pinfunction "1_1") (pintype "passive"))
      (node (ref "T1") (pin "2") (pinfunction "B_2") (pintype "passive"))
    )
    (net (code "52") (name "Net-(T1-C)") (class "Default")
      (node (ref "D6") (pin "A") (pinfunction "A_A") (pintype "passive"))
      (node (ref "FAN") (pin "2") (pinfunction "2_2") (pintype "passive"))
      (node (ref "T1") (pin "1") (pinfunction "C_1") (pintype "passive"))
    )
    (net (code "53") (name "PWM_C") (class "Default")
      (node (ref "ARDUINO_NANO1") (pin "27") (pinfunction "D9/OC1A_27") (pintype "bidirectional"))
      (node (ref "R34") (pin "2") (pinfunction "2_2") (pintype "passive"))
    )
    (net (code "54") (name "PWM_V") (class "Default")
      (node (ref "ARDUINO_NANO1") (pin "28") (pinfunction "D10/OC1B/~{SS}_28") (pintype "bidirectional"))
      (node (ref "R33") (pin "2") (pinfunction "2_2") (pintype "passive"))
    )
    (net (code "55") (name "SERIAL_RX") (class "Default")
      (node (ref "OK1") (pin "6") (pinfunction "VO_6") (pintype "passive"))
      (node (ref "R38") (pin "2") (pinfunction "2_2") (pintype "passive"))
      (node (ref "SJ2") (pin "2") (pinfunction "2_2") (pintype "passive"))
    )
    (net (code "56") (name "SERIAL_TX") (class "Default")
      (node (ref "SJ1") (pin "2") (pinfunction "2_2") (pintype "passive"))
      (node (ref "TX") (pin "1") (pinfunction "1_1") (pintype "passive"))
    )
    (net (code "57") (name "TEMP") (class "Default")
      (node (ref "ARDUINO_NANO1") (pin "11") (pinfunction "ADC7/A7_11") (pintype "bidirectional"))
      (node (ref "NTC") (pin "1") (pinfunction "1_1") (pintype "passive"))
      (node (ref "R35") (pin "2") (pinfunction "2_2") (pintype "passive"))
    )
    (net (code "58") (name "VCC_5V") (class "Default")
      (node (ref "ARDUINO_NANO1") (pin "12") (pinfunction "5V_12") (pintype "power_in"))
      (node (ref "C12") (pin "1") (pinfunction "1_1") (pintype "passive"))
      (node (ref "IC5") (pin "3") (pinfunction "VO_3") (pintype "passive"))
      (node (ref "JP7") (pin "2") (pinfunction "2_2") (pintype "passive"))
      (node (ref "JP7") (pin "4") (pinfunction "4_4") (pintype "passive"))
      (node (ref "OK1") (pin "8") (pinfunction "VCC_8") (pintype "passive"))
      (node (ref "R35") (pin "1") (pinfunction "1_1") (pintype "passive"))
      (node (ref "R37") (pin "1") (pinfunction "1_1") (pintype "passive"))
      (node (ref "R38") (pin "1") (pinfunction "1_1") (pintype "passive"))
      (node (ref "TX") (pin "2") (pinfunction "2_2") (pintype "passive"))
    )
    (net (code "59") (name "VCC_8V") (class "Default")
      (node (ref "C13") (pin "1") (pinfunction "1_1") (pintype "passive"))
      (node (ref "IC1") (pin "8") (pinfunction "V+_8") (pintype "power_in"))
      (node (ref "IC2") (pin "8") (pinfunction "V+_8") (pintype "power_in"))
      (node (ref "IC4") (pin "3") (pinfunction "VO_3") (pintype "passive"))
      (node (ref "R16") (pin "1") (pinfunction "1_1") (pintype "passive"))
      (node (ref "R25") (pin "2") (pinfunction "2_2") (pintype "passive"))
      (node (ref "R29") (pin "2") (pinfunction "2_2") (pintype "passive"))
      (node (ref "R5") (pin "2") (pinfunction "2_2") (pintype "passive"))
    )
    (net (code "60") (name "VCC_12V") (class "Default")
      (node (ref "C11") (pin "1") (pinfunction "1_1") (pintype "passive"))
      (node (ref "D6") (pin "C") (pinfunction "C_C") (pintype "passive"))
      (node (ref "FAN") (pin "1") (pinfunction "1_1") (pintype "passive"))
      (node (ref "IC3") (pin "3") (pinfunction "VO_3") (pintype "passive"))
    )
    (net (code "61") (name "VIN") (class "Default")
      (node (ref "ARDUINO_NANO1") (pin "15") (pinfunction "VIN_15") (pintype "power_in"))
    )
    (net (code "62") (name "V_MEAS") (class "Default")
      (node (ref "ARDUINO_NANO1") (pin "4") (pinfunction "ADC0/A0_4") (pintype "bidirectional"))
      (node (ref "C4") (pin "2") (pinfunction "2_2") (pintype "passive"))
      (node (ref "IC1") (pin "6") (pinfunction "-IN_6") (pintype "input"))
      (node (ref "R21") (pin "1") (pinfunction "1_1") (pintype "passive"))
      (node (ref "R22") (pin "2") (pinfunction "2_2") (pintype "passive"))
    )
    (net (code "63") (name "V_SET") (class "Default")
      (node (ref "C16") (pin "1") (pinfunction "1_1") (pintype "passive"))
      (node (ref "C6") (pin "2") (pinfunction "2_2") (pintype "passive"))
      (node (ref "IC1") (pin "5") (pinfunction "+IN_5") (pintype "input"))
      (node (ref "R39") (pin "1") (pinfunction "1_1") (pintype "passive"))
    )
    (net (code "64") (name "unconnected-(ARDUINO_NANO1-3V3-Pad2)") (class "Default")
      (node (ref "ARDUINO_NANO1") (pin "2") (pinfunction "3V3_2") (pintype "output"))
    )
    (net (code "65") (name "unconnected-(ARDUINO_NANO1-AREF-Pad3)") (class "Default")
      (node (ref "ARDUINO_NANO1") (pin "3") (pinfunction "AREF_3") (pintype "input"))
    )
    (net (code "66") (name "unconnected-(ARDUINO_NANO1-~{RESET}-Pad13)") (class "Default")
      (node (ref "ARDUINO_NANO1") (pin "13") (pinfunction "~{RESET}_13") (pintype "input"))
    )
    (net (code "67") (name "unconnected-(ARDUINO_NANO1-~{RESET}-Pad18)") (class "Default")
      (node (ref "ARDUINO_NANO1") (pin "18") (pinfunction "~{RESET}_18") (pintype "input"))
    )
  )
)
